# LiPoKiller_Panel.net
KiCad netlist of a schematic drawn in Altium Designer
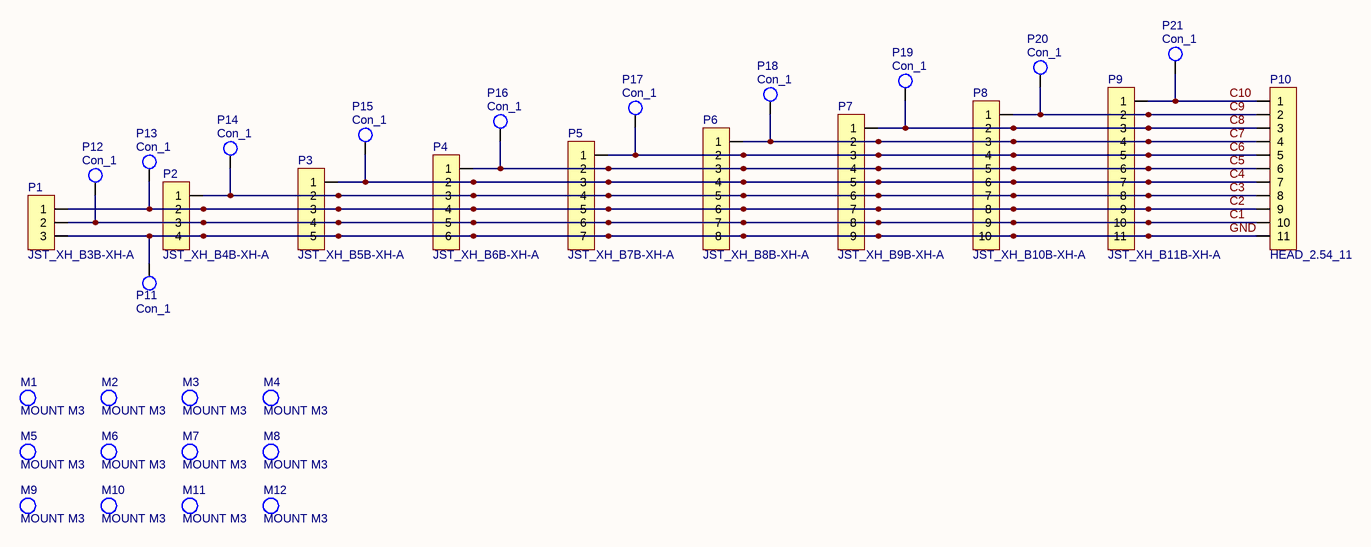
[diagram p0: LiPoKiller_Panel.SchDoc]

(export (version "E")
  (design (tool "Eeschema 10.0.6"))
  (components
    (comp (ref "M1")
      (value "MOUNT M3")
      (footprint "LiPoKiller:MOUNT_M3")
      (description "Mounting hole M3")
      (libsource (lib "LiPoKiller") (part "MOUNT M3"))
    )
    (comp (ref "M2")
      (value "MOUNT M3")
      (footprint "LiPoKiller:MOUNT_M3")
      (description "Mounting hole M3")
      (libsource (lib "LiPoKiller") (part "MOUNT M3"))
    )
    (comp (ref "M3")
      (value "MOUNT M3")
      (footprint "LiPoKiller:MOUNT_M3")
      (description "Mounting hole M3")
      (libsource (lib "LiPoKiller") (part "MOUNT M3"))
    )
    (comp (ref "M4")
      (value "MOUNT M3")
      (footprint "LiPoKiller:MOUNT_M3")
      (description "Mounting hole M3")
      (libsource (lib "LiPoKiller") (part "MOUNT M3"))
    )
    (comp (ref "M5")
      (value "MOUNT M3")
      (footprint "LiPoKiller:MOUNT_M3")
      (description "Mounting hole M3")
      (libsource (lib "LiPoKiller") (part "MOUNT M3"))
    )
    (comp (ref "M6")
      (value "MOUNT M3")
      (footprint "LiPoKiller:MOUNT_M3")
      (description "Mounting hole M3")
      (libsource (lib "LiPoKiller") (part "MOUNT M3"))
    )
    (comp (ref "M7")
      (value "MOUNT M3")
      (footprint "LiPoKiller:MOUNT_M3")
      (description "Mounting hole M3")
      (libsource (lib "LiPoKiller") (part "MOUNT M3"))
    )
    (comp (ref "M8")
      (value "MOUNT M3")
      (footprint "LiPoKiller:MOUNT_M3")
      (description "Mounting hole M3")
      (libsource (lib "LiPoKiller") (part "MOUNT M3"))
    )
    (comp (ref "M9")
      (value "MOUNT M3")
      (footprint "LiPoKiller:MOUNT_M3")
      (description "Mounting hole M3")
      (libsource (lib "LiPoKiller") (part "MOUNT M3"))
    )
    (comp (ref "M10")
      (value "MOUNT M3")
      (footprint "LiPoKiller:MOUNT_M3")
      (description "Mounting hole M3")
      (libsource (lib "LiPoKiller") (part "MOUNT M3"))
    )
    (comp (ref "M11")
      (value "MOUNT M3")
      (footprint "LiPoKiller:MOUNT_M3")
      (description "Mounting hole M3")
      (libsource (lib "LiPoKiller") (part "MOUNT M3"))
    )
    (comp (ref "M12")
      (value "MOUNT M3")
      (footprint "LiPoKiller:MOUNT_M3")
      (description "Mounting hole M3")
      (libsource (lib "LiPoKiller") (part "MOUNT M3"))
    )
    (comp (ref "P1")
      (value "JST_XH_B3B-XH-A")
      (footprint "LiPoKiller:CON_JST_XH_B3B-XH-A")
      (libsource (lib "LiPoKiller") (part "JST_XH_B3B-XH-A"))
    )
    (comp (ref "P2")
      (value "JST_XH_B4B-XH-A")
      (footprint "LiPoKiller:CON_JST_XH_B4B-XH-A")
      (libsource (lib "LiPoKiller") (part "JST_XH_B4B-XH-A"))
    )
    (comp (ref "P3")
      (value "JST_XH_B5B-XH-A")
      (footprint "LiPoKiller:CON_JST_XH_B5B-XH-A")
      (libsource (lib "LiPoKiller") (part "JST_XH_B5B-XH-A"))
    )
    (comp (ref "P4")
      (value "JST_XH_B6B-XH-A")
      (footprint "LiPoKiller:CON_JST_XH_B6B-XH-A")
      (libsource (lib "LiPoKiller") (part "JST_XH_B6B-XH-A"))
    )
    (comp (ref "P5")
      (value "JST_XH_B7B-XH-A")
      (footprint "LiPoKiller:CON_JST_XH_B7B-XH-A")
      (libsource (lib "LiPoKiller") (part "JST_XH_B7B-XH-A"))
    )
    (comp (ref "P6")
      (value "JST_XH_B8B-XH-A")
      (footprint "LiPoKiller:CON_JST_XH_B8B-XH-A")
      (libsource (lib "LiPoKiller") (part "JST_XH_B8B-XH-A"))
    )
    (comp (ref "P7")
      (value "JST_XH_B9B-XH-A")
      (footprint "LiPoKiller:CON_JST_XH_B9B-XH-A")
      (libsource (lib "LiPoKiller") (part "JST_XH_B9B-XH-A"))
    )
    (comp (ref "P8")
      (value "JST_XH_B10B-XH-A")
      (footprint "LiPoKiller:CON_JST_XH_B10B-XH-A")
      (libsource (lib "LiPoKiller") (part "JST_XH_B10B-XH-A"))
    )
    (comp (ref "P9")
      (value "JST_XH_B11B-XH-A")
      (footprint "LiPoKiller:CON_JST_XH_B11B-XH-A")
      (libsource (lib "LiPoKiller") (part "JST_XH_B11B-XH-A"))
    )
    (comp (ref "P10")
      (value "HEAD_2.54_11")
      (footprint "LiPoKiller:CON_HEAD_2.54_11")
      (libsource (lib "LiPoKiller") (part "HEAD_2.54_11"))
    )
    (comp (ref "P11")
      (value "Con_1")
      (footprint "LiPoKiller:Con_1_2MM_4MM")
      (libsource (lib "LiPoKiller") (part "Con_1"))
    )
    (comp (ref "P12")
      (value "Con_1")
      (footprint "LiPoKiller:Con_1_2MM_4MM")
      (libsource (lib "LiPoKiller") (part "Con_1"))
    )
    (comp (ref "P13")
      (value "Con_1")
      (footprint "LiPoKiller:Con_1_2MM_4MM")
      (libsource (lib "LiPoKiller") (part "Con_1"))
    )
    (comp (ref "P14")
      (value "Con_1")
      (footprint "LiPoKiller:Con_1_2MM_4MM")
      (libsource (lib "LiPoKiller") (part "Con_1"))
    )
    (comp (ref "P15")
      (value "Con_1")
      (footprint "LiPoKiller:Con_1_2MM_4MM")
      (libsource (lib "LiPoKiller") (part "Con_1"))
    )
    (comp (ref "P16")
      (value "Con_1")
      (footprint "LiPoKiller:Con_1_2MM_4MM")
      (libsource (lib "LiPoKiller") (part "Con_1"))
    )
    (comp (ref "P17")
      (value "Con_1")
      (footprint "LiPoKiller:Con_1_2MM_4MM")
      (libsource (lib "LiPoKiller") (part "Con_1"))
    )
    (comp (ref "P18")
      (value "Con_1")
      (footprint "LiPoKiller:Con_1_2MM_4MM")
      (libsource (lib "LiPoKiller") (part "Con_1"))
    )
    (comp (ref "P19")
      (value "Con_1")
      (footprint "LiPoKiller:Con_1_2MM_4MM")
      (libsource (lib "LiPoKiller") (part "Con_1"))
    )
    (comp (ref "P20")
      (value "Con_1")
      (footprint "LiPoKiller:Con_1_2MM_4MM")
      (libsource (lib "LiPoKiller") (part "Con_1"))
    )
    (comp (ref "P21")
      (value "Con_1")
      (footprint "LiPoKiller:Con_1_2MM_4MM")
      (libsource (lib "LiPoKiller") (part "Con_1"))
    )
  )
  (nets
    (net (code "1") (name "/C1") (class "Default")
      (node (ref "P1") (pin "2") (pinfunction "2_2") (pintype "passive"))
      (node (ref "P10") (pin "10") (pinfunction "10_10") (pintype "passive"))
      (node (ref "P12") (pin "1") (pinfunction "1_1") (pintype "passive"))
      (node (ref "P2") (pin "3") (pinfunction "3_3") (pintype "passive"))
      (node (ref "P3") (pin "4") (pinfunction "4_4") (pintype "passive"))
      (node (ref "P4") (pin "5") (pinfunction "5_5") (pintype "passive"))
      (node (ref "P5") (pin "6") (pinfunction "6_6") (pintype "passive"))
      (node (ref "P6") (pin "7") (pinfunction "7_7") (pintype "passive"))
      (node (ref "P7") (pin "8") (pinfunction "8_8") (pintype "passive"))
      (node (ref "P8") (pin "9") (pinfunction "9_9") (pintype "passive"))
      (node (ref "P9") (pin "10") (pinfunction "10_10") (pintype "passive"))
    )
    (net (code "2") (name "/C2") (class "Default")
      (node (ref "P1") (pin "1") (pinfunction "1_1") (pintype "passive"))
      (node (ref "P10") (pin "9") (pinfunction "9_9") (pintype "passive"))
      (node (ref "P13") (pin "1") (pinfunction "1_1") (pintype "passive"))
      (node (ref "P2") (pin "2") (pinfunction "2_2") (pintype "passive"))
      (node (ref "P3") (pin "3") (pinfunction "3_3") (pintype "passive"))
      (node (ref "P4") (pin "4") (pinfunction "4_4") (pintype "passive"))
      (node (ref "P5") (pin "5") (pinfunction "5_5") (pintype "passive"))
      (node (ref "P6") (pin "6") (pinfunction "6_6") (pintype "passive"))
      (node (ref "P7") (pin "7") (pinfunction "7_7") (pintype "passive"))
      (node (ref "P8") (pin "8") (pinfunction "8_8") (pintype "passive"))
      (node (ref "P9") (pin "9") (pinfunction "9_9") (pintype "passive"))
    )
    (net (code "3") (name "/C3") (class "Default")
      (node (ref "P10") (pin "8") (pinfunction "8_8") (pintype "passive"))
      (node (ref "P14") (pin "1") (pinfunction "1_1") (pintype "passive"))
      (node (ref "P2") (pin "1") (pinfunction "1_1") (pintype "passive"))
      (node (ref "P3") (pin "2") (pinfunction "2_2") (pintype "passive"))
      (node (ref "P4") (pin "3") (pinfunction "3_3") (pintype "passive"))
      (node (ref "P5") (pin "4") (pinfunction "4_4") (pintype "passive"))
      (node (ref "P6") (pin "5") (pinfunction "5_5") (pintype "passive"))
      (node (ref "P7") (pin "6") (pinfunction "6_6") (pintype "passive"))
      (node (ref "P8") (pin "7") (pinfunction "7_7") (pintype "passive"))
      (node (ref "P9") (pin "8") (pinfunction "8_8") (pintype "passive"))
    )
    (net (code "4") (name "/C4") (class "Default")
      (node (ref "P10") (pin "7") (pinfunction "7_7") (pintype "passive"))
      (node (ref "P15") (pin "1") (pinfunction "1_1") (pintype "passive"))
      (node (ref "P3") (pin "1") (pinfunction "1_1") (pintype "passive"))
      (node (ref "P4") (pin "2") (pinfunction "2_2") (pintype "passive"))
      (node (ref "P5") (pin "3") (pinfunction "3_3") (pintype "passive"))
      (node (ref "P6") (pin "4") (pinfunction "4_4") (pintype "passive"))
      (node (ref "P7") (pin "5") (pinfunction "5_5") (pintype "passive"))
      (node (ref "P8") (pin "6") (pinfunction "6_6") (pintype "passive"))
      (node (ref "P9") (pin "7") (pinfunction "7_7") (pintype "passive"))
    )
    (net (code "5") (name "/C5") (class "Default")
      (node (ref "P10") (pin "6") (pinfunction "6_6") (pintype "passive"))
      (node (ref "P16") (pin "1") (pinfunction "1_1") (pintype "passive"))
      (node (ref "P4") (pin "1") (pinfunction "1_1") (pintype "passive"))
      (node (ref "P5") (pin "2") (pinfunction "2_2") (pintype "passive"))
      (node (ref "P6") (pin "3") (pinfunction "3_3") (pintype "passive"))
      (node (ref "P7") (pin "4") (pinfunction "4_4") (pintype "passive"))
      (node (ref "P8") (pin "5") (pinfunction "5_5") (pintype "passive"))
      (node (ref "P9") (pin "6") (pinfunction "6_6") (pintype "passive"))
    )
    (net (code "6") (name "/C6") (class "Default")
      (node (ref "P10") (pin "5") (pinfunction "5_5") (pintype "passive"))
      (node (ref "P17") (pin "1") (pinfunction "1_1") (pintype "passive"))
      (node (ref "P5") (pin "1") (pinfunction "1_1") (pintype "passive"))
      (node (ref "P6") (pin "2") (pinfunction "2_2") (pintype "passive"))
      (node (ref "P7") (pin "3") (pinfunction "3_3") (pintype "passive"))
      (node (ref "P8") (pin "4") (pinfunction "4_4") (pintype "passive"))
      (node (ref "P9") (pin "5") (pinfunction "5_5") (pintype "passive"))
    )
    (net (code "7") (name "/C7") (class "Default")
      (node (ref "P10") (pin "4") (pinfunction "4_4") (pintype "passive"))
      (node (ref "P18") (pin "1") (pinfunction "1_1") (pintype "passive"))
      (node (ref "P6") (pin "1") (pinfunction "1_1") (pintype "passive"))
      (node (ref "P7") (pin "2") (pinfunction "2_2") (pintype "passive"))
      (node (ref "P8") (pin "3") (pinfunction "3_3") (pintype "passive"))
      (node (ref "P9") (pin "4") (pinfunction "4_4") (pintype "passive"))
    )
    (net (code "8") (name "/C8") (class "Default")
      (node (ref "P10") (pin "3") (pinfunction "3_3") (pintype "passive"))
      (node (ref "P19") (pin "1") (pinfunction "1_1") (pintype "passive"))
      (node (ref "P7") (pin "1") (pinfunction "1_1") (pintype "passive"))
      (node (ref "P8") (pin "2") (pinfunction "2_2") (pintype "passive"))
      (node (ref "P9") (pin "3") (pinfunction "3_3") (pintype "passive"))
    )
    (net (code "9") (name "/C9") (class "Default")
      (node (ref "P10") (pin "2") (pinfunction "2_2") (pintype "passive"))
      (node (ref "P20") (pin "1") (pinfunction "1_1") (pintype "passive"))
      (node (ref "P8") (pin "1") (pinfunction "1_1") (pintype "passive"))
      (node (ref "P9") (pin "2") (pinfunction "2_2") (pintype "passive"))
    )
    (net (code "10") (name "/C10") (class "Default")
      (node (ref "P10") (pin "1") (pinfunction "1_1") (pintype "passive"))
      (node (ref "P21") (pin "1") (pinfunction "1_1") (pintype "passive"))
      (node (ref "P9") (pin "1") (pinfunction "1_1") (pintype "passive"))
    )
    (net (code "11") (name "/GND") (class "Default")
      (node (ref "P1") (pin "3") (pinfunction "3_3") (pintype "passive"))
      (node (ref "P10") (pin "11") (pinfunction "11_11") (pintype "passive"))
      (node (ref "P11") (pin "1") (pinfunction "1_1") (pintype "passive"))
      (node (ref "P2") (pin "4") (pinfunction "4_4") (pintype "passive"))
      (node (ref "P3") (pin "5") (pinfunction "5_5") (pintype "passive"))
      (node (ref "P4") (pin "6") (pinfunction "6_6") (pintype "passive"))
      (node (ref "P5") (pin "7") (pinfunction "7_7") (pintype "passive"))
      (node (ref "P6") (pin "8") (pinfunction "8_8") (pintype "passive"))
      (node (ref "P7") (pin "9") (pinfunction "9_9") (pintype "passive"))
      (node (ref "P8") (pin "10") (pinfunction "10_10") (pintype "passive"))
      (node (ref "P9") (pin "11") (pinfunction "11_11") (pintype "passive"))
    )
  )
)
